# mini64se-v1_0_9-103-2s.net
KiCad netlist of a schematic drawn in EAGLE
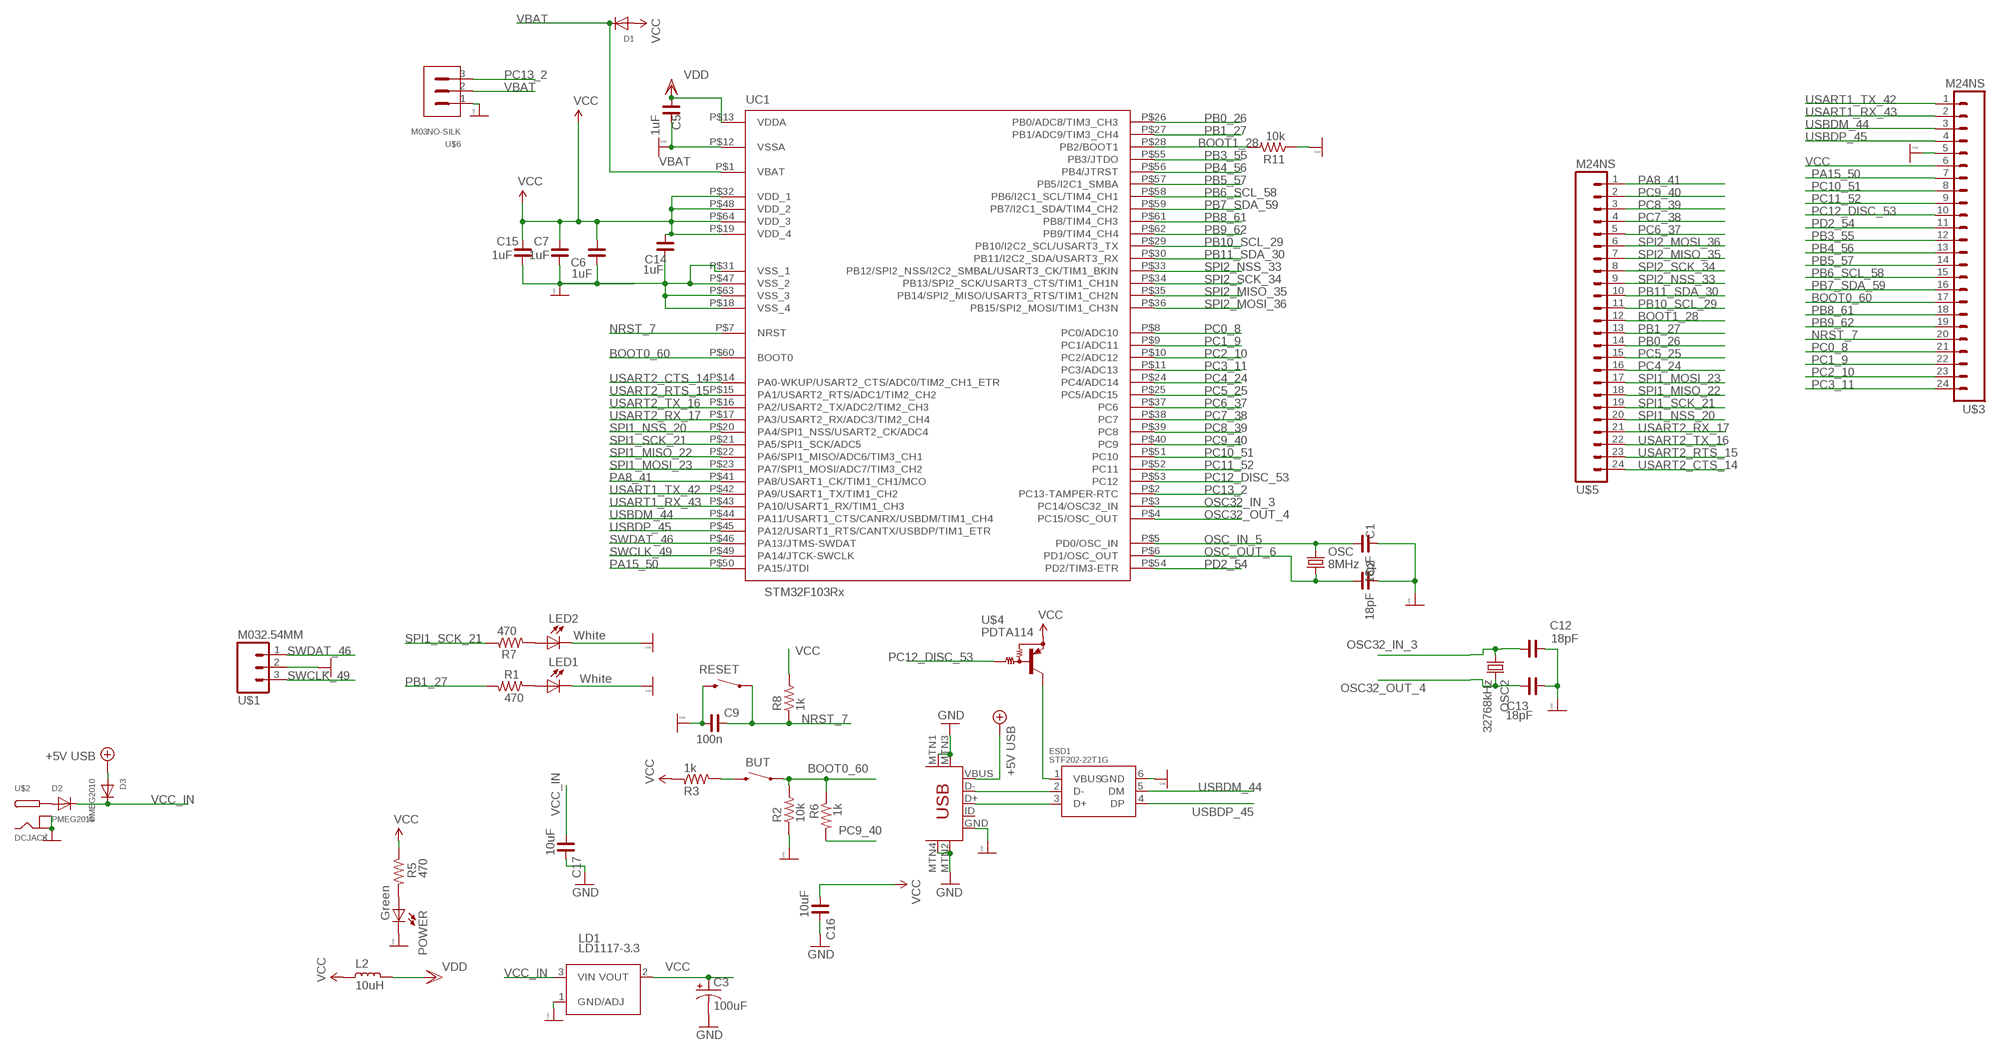
[diagram p0: schematic, sheet 1]

(export (version "E")
  (design (tool "Eeschema 10.0.6"))
  (components
    (comp (ref "BUT")
      (value "SWITCH-MOMENTARY-2SMD")
      (footprint "eagle-import:TACTILE_SWITCH_SMD")
      (libsource (lib "eagle-import") (part "SWITCH-MOMENTARY-2SMD"))
    )
    (comp (ref "C1")
      (value "18pF")
      (footprint "eagle-import:C0603")
      (libsource (lib "eagle-import") (part "C_0603"))
    )
    (comp (ref "C2")
      (value "18pF")
      (footprint "eagle-import:C0603")
      (libsource (lib "eagle-import") (part "C_0603"))
    )
    (comp (ref "C3")
      (value "100uF")
      (footprint "eagle-import:PANASONIC_C")
      (libsource (lib "eagle-import") (part "CAP_POLC"))
    )
    (comp (ref "C5")
      (value "1uF")
      (footprint "eagle-import:C0603")
      (libsource (lib "eagle-import") (part "C_0603"))
    )
    (comp (ref "C6")
      (value "1uF")
      (footprint "eagle-import:C0603")
      (libsource (lib "eagle-import") (part "C_0603"))
    )
    (comp (ref "C7")
      (value "1uF")
      (footprint "eagle-import:C0603")
      (libsource (lib "eagle-import") (part "C_0603"))
    )
    (comp (ref "C9")
      (value "100n")
      (footprint "eagle-import:C0603")
      (libsource (lib "eagle-import") (part "C_0603"))
    )
    (comp (ref "C12")
      (value "18pF")
      (footprint "eagle-import:C0603")
      (libsource (lib "eagle-import") (part "C_0603"))
    )
    (comp (ref "C13")
      (value "18pF")
      (footprint "eagle-import:C0603")
      (libsource (lib "eagle-import") (part "C_0603"))
    )
    (comp (ref "C14")
      (value "1uF")
      (footprint "eagle-import:C0603")
      (libsource (lib "eagle-import") (part "C_0603"))
    )
    (comp (ref "C15")
      (value "1uF")
      (footprint "eagle-import:C0603")
      (libsource (lib "eagle-import") (part "C_0603"))
    )
    (comp (ref "C16")
      (value "10uF")
      (footprint "eagle-import:C0805")
      (libsource (lib "eagle-import") (part "C_0805"))
    )
    (comp (ref "C17")
      (value "10uF")
      (footprint "eagle-import:C0805")
      (libsource (lib "eagle-import") (part "C_0805"))
    )
    (comp (ref "D1")
      (value "DIODESOD-323")
      (footprint "eagle-import:SOD-323")
      (libsource (lib "eagle-import") (part "DIODESOD-323"))
    )
    (comp (ref "D2")
      (value "PMEG2010")
      (footprint "eagle-import:SOD-323")
      (libsource (lib "eagle-import") (part "DIODESOD-323"))
    )
    (comp (ref "D3")
      (value "PMEG2010")
      (footprint "eagle-import:SOD-323")
      (libsource (lib "eagle-import") (part "DIODESOD-323"))
    )
    (comp (ref "ESD1")
      (value "STF202-22T1G")
      (footprint "eagle-import:TSOP-6")
      (libsource (lib "eagle-import") (part "STF202TSOP-6"))
    )
    (comp (ref "L2")
      (value "10uH")
      (footprint "eagle-import:PM0603")
      (libsource (lib "eagle-import") (part "L_PM0603"))
    )
    (comp (ref "LD1")
      (value "LD1117-3.3")
      (footprint "eagle-import:SOT223")
      (libsource (lib "eagle-import") (part "LD1117SOT223"))
    )
    (comp (ref "LED1")
      (value "White")
      (footprint "eagle-import:KA-3528ASYC")
      (libsource (lib "eagle-import") (part "LEDKA-3528ASYC"))
    )
    (comp (ref "LED2")
      (value "White")
      (footprint "eagle-import:KA-3528ASYC")
      (libsource (lib "eagle-import") (part "LEDKA-3528ASYC"))
    )
    (comp (ref "OSC")
      (value "8MHz")
      (footprint "eagle-import:HC49U-V")
      (libsource (lib "eagle-import") (part "CRYSTALHC49UV"))
    )
    (comp (ref "OSC2")
      (value "32768kHz")
      (footprint "eagle-import:TC26H-M")
      (libsource (lib "eagle-import") (part "CRYSTALTC26HM"))
    )
    (comp (ref "POWER")
      (value "Green")
      (footprint "eagle-import:CHIPLED_0603")
      (libsource (lib "eagle-import") (part "LEDCHIPLED_0603"))
    )
    (comp (ref "R1")
      (value "470")
      (footprint "eagle-import:R0603")
      (libsource (lib "eagle-import") (part "R_0603"))
    )
    (comp (ref "R2")
      (value "10k")
      (footprint "eagle-import:R0603")
      (libsource (lib "eagle-import") (part "R_0603"))
    )
    (comp (ref "R3")
      (value "1k")
      (footprint "eagle-import:R0603")
      (libsource (lib "eagle-import") (part "R_0603"))
    )
    (comp (ref "R5")
      (value "470")
      (footprint "eagle-import:R0603")
      (libsource (lib "eagle-import") (part "R_0603"))
    )
    (comp (ref "R6")
      (value "1k")
      (footprint "eagle-import:R0603")
      (libsource (lib "eagle-import") (part "R_0603"))
    )
    (comp (ref "R7")
      (value "470")
      (footprint "eagle-import:R0603")
      (libsource (lib "eagle-import") (part "R_0603"))
    )
    (comp (ref "R8")
      (value "1k")
      (footprint "eagle-import:R0603")
      (libsource (lib "eagle-import") (part "R_0603"))
    )
    (comp (ref "R11")
      (value "10k")
      (footprint "eagle-import:R0603")
      (libsource (lib "eagle-import") (part "R_0603"))
    )
    (comp (ref "RESET")
      (value "SWITCH-MOMENTARY-2SMD")
      (footprint "eagle-import:TACTILE_SWITCH_SMD")
      (libsource (lib "eagle-import") (part "SWITCH-MOMENTARY-2SMD"))
    )
    (comp (ref "U$1")
      (value "M032.54MM")
      (footprint "eagle-import:1X03_NO_SILK")
      (libsource (lib "eagle-import") (part "M031X03_NO_SILK"))
    )
    (comp (ref "U$2")
      (value "DCJACK")
      (footprint "eagle-import:DC-020-001")
      (libsource (lib "eagle-import") (part "DCJACK"))
    )
    (comp (ref "U$3")
      (value "M24NS")
      (footprint "eagle-import:1X24_NO_SILK")
      (libsource (lib "eagle-import") (part "M24NS"))
    )
    (comp (ref "U$4")
      (value "PDTA114")
      (footprint "eagle-import:SOT23-3")
      (libsource (lib "eagle-import") (part "PNP-DRIVERSOT23-3"))
    )
    (comp (ref "U$5")
      (value "M24NS")
      (footprint "eagle-import:1X24_NO_SILK")
      (libsource (lib "eagle-import") (part "M24NS"))
    )
    (comp (ref "U$6")
      (value "M03NO-SILK")
      (footprint "eagle-import:1X03_NO_SILK")
      (libsource (lib "eagle-import") (part "M03NO-SILK"))
    )
    (comp (ref "UC1")
      (value "STM32F103Rx")
      (footprint "eagle-import:TQFP-10X10-64")
      (libsource (lib "eagle-import") (part "STM32F103"))
    )
    (comp (ref "USB")
      (value "USB-MINIB-5PIN")
      (footprint "eagle-import:USB-MINIB")
      (libsource (lib "eagle-import") (part "USB-MINIB-5PIN"))
    )
  )
  (nets
    (net (code "1") (name "+5V USB") (class "Default")
      (node (ref "D3") (pin "A") (pinfunction "A_A") (pintype "passive"))
      (node (ref "USB") (pin "VBUS") (pinfunction "VBUS_VBUS") (pintype "bidirectional"))
    )
    (net (code "2") (name "/BOOT0_60") (class "Default")
      (node (ref "BUT") (pin "1") (pinfunction "1_1") (pintype "passive"))
      (node (ref "R2") (pin "2") (pinfunction "2_2") (pintype "passive"))
      (node (ref "R6") (pin "1") (pinfunction "1_1") (pintype "passive"))
      (node (ref "U$3") (pin "17") (pinfunction "18_17") (pintype "passive"))
      (node (ref "UC1") (pin "P$60") (pinfunction "BOOT0_P$60") (pintype "bidirectional"))
    )
    (net (code "3") (name "/BOOT1_28") (class "Default")
      (node (ref "R11") (pin "2") (pinfunction "2_2") (pintype "passive"))
      (node (ref "U$5") (pin "12") (pinfunction "13_12") (pintype "passive"))
      (node (ref "UC1") (pin "P$28") (pinfunction "PB2/BOOT1_P$28") (pintype "bidirectional"))
    )
    (net (code "4") (name "/NRST_7") (class "Default")
      (node (ref "C9") (pin "2") (pinfunction "2_2") (pintype "passive"))
      (node (ref "R8") (pin "1") (pinfunction "1_1") (pintype "passive"))
      (node (ref "RESET") (pin "1") (pinfunction "1_1") (pintype "passive"))
      (node (ref "U$3") (pin "20") (pinfunction "21_20") (pintype "passive"))
      (node (ref "UC1") (pin "P$7") (pinfunction "NRST_P$7") (pintype "bidirectional"))
    )
    (net (code "5") (name "/OSC32_IN_3") (class "Default")
      (node (ref "C12") (pin "2") (pinfunction "2_2") (pintype "passive"))
      (node (ref "OSC2") (pin "1") (pinfunction "1_1") (pintype "passive"))
      (node (ref "UC1") (pin "P$3") (pinfunction "PC14/OSC32_IN_P$3") (pintype "bidirectional"))
    )
    (net (code "6") (name "/OSC32_OUT_4") (class "Default")
      (node (ref "C13") (pin "2") (pinfunction "2_2") (pintype "passive"))
      (node (ref "OSC2") (pin "2") (pinfunction "2_2") (pintype "passive"))
      (node (ref "UC1") (pin "P$4") (pinfunction "PC15/OSC_OUT_P$4") (pintype "bidirectional"))
    )
    (net (code "7") (name "/OSC_IN_5") (class "Default")
      (node (ref "C1") (pin "2") (pinfunction "2_2") (pintype "passive"))
      (node (ref "OSC") (pin "2") (pinfunction "2_2") (pintype "passive"))
      (node (ref "UC1") (pin "P$5") (pinfunction "PD0/OSC_IN_P$5") (pintype "bidirectional"))
    )
    (net (code "8") (name "/OSC_OUT_6") (class "Default")
      (node (ref "C2") (pin "2") (pinfunction "2_2") (pintype "passive"))
      (node (ref "OSC") (pin "1") (pinfunction "1_1") (pintype "passive"))
      (node (ref "UC1") (pin "P$6") (pinfunction "PD1/OSC_OUT_P$6") (pintype "bidirectional"))
    )
    (net (code "9") (name "/PA8_41") (class "Default")
      (node (ref "U$5") (pin "1") (pinfunction "2_1") (pintype "passive"))
      (node (ref "UC1") (pin "P$41") (pinfunction "PA8/USART1_CK/TIM1_CH1/MCO_P$41") (pintype "bidirectional"))
    )
    (net (code "10") (name "/PA15_50") (class "Default")
      (node (ref "U$3") (pin "7") (pinfunction "8_7") (pintype "passive"))
      (node (ref "UC1") (pin "P$50") (pinfunction "PA15/JTDI_P$50") (pintype "bidirectional"))
    )
    (net (code "11") (name "/PB0_26") (class "Default")
      (node (ref "U$5") (pin "14") (pinfunction "15_14") (pintype "passive"))
      (node (ref "UC1") (pin "P$26") (pinfunction "PB0/ADC8/TIM3_CH3_P$26") (pintype "bidirectional"))
    )
    (net (code "12") (name "/PB1_27") (class "Default")
      (node (ref "R1") (pin "2") (pinfunction "2_2") (pintype "passive"))
      (node (ref "U$5") (pin "13") (pinfunction "14_13") (pintype "passive"))
      (node (ref "UC1") (pin "P$27") (pinfunction "PB1/ADC9/TIM3_CH4_P$27") (pintype "bidirectional"))
    )
    (net (code "13") (name "/PB3_55") (class "Default")
      (node (ref "U$3") (pin "12") (pinfunction "13_12") (pintype "passive"))
      (node (ref "UC1") (pin "P$55") (pinfunction "PB3/JTDO_P$55") (pintype "bidirectional"))
    )
    (net (code "14") (name "/PB4_56") (class "Default")
      (node (ref "U$3") (pin "13") (pinfunction "14_13") (pintype "passive"))
      (node (ref "UC1") (pin "P$56") (pinfunction "PB4/JTRST_P$56") (pintype "bidirectional"))
    )
    (net (code "15") (name "/PB5_57") (class "Default")
      (node (ref "U$3") (pin "14") (pinfunction "15_14") (pintype "passive"))
      (node (ref "UC1") (pin "P$57") (pinfunction "PB5/I2C1_SMBA_P$57") (pintype "bidirectional"))
    )
    (net (code "16") (name "/PB6_SCL_58") (class "Default")
      (node (ref "U$3") (pin "15") (pinfunction "16_15") (pintype "passive"))
      (node (ref "UC1") (pin "P$58") (pinfunction "PB6/I2C1_SCL/TIM4_CH1_P$58") (pintype "bidirectional"))
    )
    (net (code "17") (name "/PB7_SDA_59") (class "Default")
      (node (ref "U$3") (pin "16") (pinfunction "17_16") (pintype "passive"))
      (node (ref "UC1") (pin "P$59") (pinfunction "PB7/I2C1_SDA/TIM4_CH2_P$59") (pintype "bidirectional"))
    )
    (net (code "18") (name "/PB8_61") (class "Default")
      (node (ref "U$3") (pin "18") (pinfunction "19_18") (pintype "passive"))
      (node (ref "UC1") (pin "P$61") (pinfunction "PB8/TIM4_CH3_P$61") (pintype "bidirectional"))
    )
    (net (code "19") (name "/PB9_62") (class "Default")
      (node (ref "U$3") (pin "19") (pinfunction "20_19") (pintype "passive"))
      (node (ref "UC1") (pin "P$62") (pinfunction "PB9/TIM4_CH4_P$62") (pintype "bidirectional"))
    )
    (net (code "20") (name "/PB10_SCL_29") (class "Default")
      (node (ref "U$5") (pin "11") (pinfunction "12_11") (pintype "passive"))
      (node (ref "UC1") (pin "P$29") (pinfunction "PB10/I2C2_SCL/USART3_TX_P$29") (pintype "bidirectional"))
    )
    (net (code "21") (name "/PB11_SDA_30") (class "Default")
      (node (ref "U$5") (pin "10") (pinfunction "11_10") (pintype "passive"))
      (node (ref "UC1") (pin "P$30") (pinfunction "PB11/I2C2_SDA/USART3_RX_P$30") (pintype "bidirectional"))
    )
    (net (code "22") (name "/PC0_8") (class "Default")
      (node (ref "U$3") (pin "21") (pinfunction "22_21") (pintype "passive"))
      (node (ref "UC1") (pin "P$8") (pinfunction "PC0/ADC10_P$8") (pintype "bidirectional"))
    )
    (net (code "23") (name "/PC1_9") (class "Default")
      (node (ref "U$3") (pin "22") (pinfunction "23_22") (pintype "passive"))
      (node (ref "UC1") (pin "P$9") (pinfunction "PC1/ADC11_P$9") (pintype "bidirectional"))
    )
    (net (code "24") (name "/PC2_10") (class "Default")
      (node (ref "U$3") (pin "23") (pinfunction "24_23") (pintype "passive"))
      (node (ref "UC1") (pin "P$10") (pinfunction "PC2/ADC12_P$10") (pintype "bidirectional"))
    )
    (net (code "25") (name "/PC3_11") (class "Default")
      (node (ref "U$3") (pin "24") (pinfunction "25_24") (pintype "passive"))
      (node (ref "UC1") (pin "P$11") (pinfunction "PC3/ADC13_P$11") (pintype "bidirectional"))
    )
    (net (code "26") (name "/PC4_24") (class "Default")
      (node (ref "U$5") (pin "16") (pinfunction "17_16") (pintype "passive"))
      (node (ref "UC1") (pin "P$24") (pinfunction "PC4/ADC14_P$24") (pintype "bidirectional"))
    )
    (net (code "27") (name "/PC5_25") (class "Default")
      (node (ref "U$5") (pin "15") (pinfunction "16_15") (pintype "passive"))
      (node (ref "UC1") (pin "P$25") (pinfunction "PC5/ADC15_P$25") (pintype "bidirectional"))
    )
    (net (code "28") (name "/PC6_37") (class "Default")
      (node (ref "U$5") (pin "5") (pinfunction "6_5") (pintype "passive"))
      (node (ref "UC1") (pin "P$37") (pinfunction "PC6_P$37") (pintype "bidirectional"))
    )
    (net (code "29") (name "/PC7_38") (class "Default")
      (node (ref "U$5") (pin "4") (pinfunction "5_4") (pintype "passive"))
      (node (ref "UC1") (pin "P$38") (pinfunction "PC7_P$38") (pintype "bidirectional"))
    )
    (net (code "30") (name "/PC8_39") (class "Default")
      (node (ref "U$5") (pin "3") (pinfunction "4_3") (pintype "passive"))
      (node (ref "UC1") (pin "P$39") (pinfunction "PC8_P$39") (pintype "bidirectional"))
    )
    (net (code "31") (name "/PC9_40") (class "Default")
      (node (ref "R6") (pin "2") (pinfunction "2_2") (pintype "passive"))
      (node (ref "U$5") (pin "2") (pinfunction "3_2") (pintype "passive"))
      (node (ref "UC1") (pin "P$40") (pinfunction "PC9_P$40") (pintype "bidirectional"))
    )
    (net (code "32") (name "/PC10_51") (class "Default")
      (node (ref "U$3") (pin "8") (pinfunction "9_8") (pintype "passive"))
      (node (ref "UC1") (pin "P$51") (pinfunction "PC10_P$51") (pintype "bidirectional"))
    )
    (net (code "33") (name "/PC11_52") (class "Default")
      (node (ref "U$3") (pin "9") (pinfunction "10_9") (pintype "passive"))
      (node (ref "UC1") (pin "P$52") (pinfunction "PC11_P$52") (pintype "bidirectional"))
    )
    (net (code "34") (name "/PC12_DISC_53") (class "Default")
      (node (ref "U$3") (pin "10") (pinfunction "11_10") (pintype "passive"))
      (node (ref "U$4") (pin "1") (pinfunction "B_1") (pintype "passive"))
      (node (ref "UC1") (pin "P$53") (pinfunction "PC12_P$53") (pintype "bidirectional"))
    )
    (net (code "35") (name "/PC13_2") (class "Default")
      (node (ref "U$6") (pin "3") (pinfunction "3_3") (pintype "bidirectional"))
      (node (ref "UC1") (pin "P$2") (pinfunction "PC13-TAMPER-RTC_P$2") (pintype "bidirectional"))
    )
    (net (code "36") (name "/PD2_54") (class "Default")
      (node (ref "U$3") (pin "11") (pinfunction "12_11") (pintype "passive"))
      (node (ref "UC1") (pin "P$54") (pinfunction "PD2/TIM3-ETR_P$54") (pintype "bidirectional"))
    )
    (net (code "37") (name "/SPI1_MISO_22") (class "Default")
      (node (ref "U$5") (pin "18") (pinfunction "19_18") (pintype "passive"))
      (node (ref "UC1") (pin "P$22") (pinfunction "PA6/SPI1_MISO/ADC6/TIM3_CH1_P$22") (pintype "bidirectional"))
    )
    (net (code "38") (name "/SPI1_MOSI_23") (class "Default")
      (node (ref "U$5") (pin "17") (pinfunction "18_17") (pintype "passive"))
      (node (ref "UC1") (pin "P$23") (pinfunction "PA7/SPI1_MOSI/ADC7/TIM3_CH2_P$23") (pintype "bidirectional"))
    )
    (net (code "39") (name "/SPI1_NSS_20") (class "Default")
      (node (ref "U$5") (pin "20") (pinfunction "21_20") (pintype "passive"))
      (node (ref "UC1") (pin "P$20") (pinfunction "PA4/SPI1_NSS/USART2_CK/ADC4_P$20") (pintype "bidirectional"))
    )
    (net (code "40") (name "/SPI1_SCK_21") (class "Default")
      (node (ref "R7") (pin "1") (pinfunction "1_1") (pintype "passive"))
      (node (ref "U$5") (pin "19") (pinfunction "20_19") (pintype "passive"))
      (node (ref "UC1") (pin "P$21") (pinfunction "PA5/SPI1_SCK/ADC5_P$21") (pintype "bidirectional"))
    )
    (net (code "41") (name "/SPI2_MISO_35") (class "Default")
      (node (ref "U$5") (pin "7") (pinfunction "8_7") (pintype "passive"))
      (node (ref "UC1") (pin "P$35") (pinfunction "PB14/SPI2_MISO/USART3_RTS/TIM1_CH2N_P$35") (pintype "bidirectional"))
    )
    (net (code "42") (name "/SPI2_MOSI_36") (class "Default")
      (node (ref "U$5") (pin "6") (pinfunction "7_6") (pintype "passive"))
      (node (ref "UC1") (pin "P$36") (pinfunction "PB15/SPI2_MOSI/TIM1_CH3N_P$36") (pintype "bidirectional"))
    )
    (net (code "43") (name "/SPI2_NSS_33") (class "Default")
      (node (ref "U$5") (pin "9") (pinfunction "10_9") (pintype "passive"))
      (node (ref "UC1") (pin "P$33") (pinfunction "PB12/SPI2_NSS/I2C2_SMBAL/USART3_CK/TIM1_BKIN_P$33") (pintype "bidirectional"))
    )
    (net (code "44") (name "/SPI2_SCK_34") (class "Default")
      (node (ref "U$5") (pin "8") (pinfunction "9_8") (pintype "passive"))
      (node (ref "UC1") (pin "P$34") (pinfunction "PB13/SPI2_SCK/USART3_CTS/TIM1_CH1N_P$34") (pintype "bidirectional"))
    )
    (net (code "45") (name "/SWCLK_49") (class "Default")
      (node (ref "U$1") (pin "3") (pinfunction "3_3") (pintype "passive"))
      (node (ref "UC1") (pin "P$49") (pinfunction "PA14/JTCK-SWCLK_P$49") (pintype "bidirectional"))
    )
    (net (code "46") (name "/SWDAT_46") (class "Default")
      (node (ref "U$1") (pin "1") (pinfunction "1_1") (pintype "passive"))
      (node (ref "UC1") (pin "P$46") (pinfunction "PA13/JTMS-SWDAT_P$46") (pintype "bidirectional"))
    )
    (net (code "47") (name "/USART1_RX_43") (class "Default")
      (node (ref "U$3") (pin "2") (pinfunction "3_2") (pintype "passive"))
      (node (ref "UC1") (pin "P$43") (pinfunction "PA10/USART1_RX/TIM1_CH3_P$43") (pintype "bidirectional"))
    )
    (net (code "48") (name "/USART1_TX_42") (class "Default")
      (node (ref "U$3") (pin "1") (pinfunction "2_1") (pintype "passive"))
      (node (ref "UC1") (pin "P$42") (pinfunction "PA9/USART1_TX/TIM1_CH2_P$42") (pintype "bidirectional"))
    )
    (net (code "49") (name "/USART2_CTS_14") (class "Default")
      (node (ref "U$5") (pin "24") (pinfunction "25_24") (pintype "passive"))
      (node (ref "UC1") (pin "P$14") (pinfunction "PA0-WKUP/USART2_CTS/ADC0/TIM2_CH1_ETR_P$14") (pintype "bidirectional"))
    )
    (net (code "50") (name "/USART2_RTS_15") (class "Default")
      (node (ref "U$5") (pin "23") (pinfunction "24_23") (pintype "passive"))
      (node (ref "UC1") (pin "P$15") (pinfunction "PA1/USART2_RTS/ADC1/TIM2_CH2_P$15") (pintype "bidirectional"))
    )
    (net (code "51") (name "/USART2_RX_17") (class "Default")
      (node (ref "U$5") (pin "21") (pinfunction "22_21") (pintype "passive"))
      (node (ref "UC1") (pin "P$17") (pinfunction "PA3/USART2_RX/ADC3/TIM2_CH4_P$17") (pintype "bidirectional"))
    )
    (net (code "52") (name "/USART2_TX_16") (class "Default")
      (node (ref "U$5") (pin "22") (pinfunction "23_22") (pintype "passive"))
      (node (ref "UC1") (pin "P$16") (pinfunction "PA2/USART2_TX/ADC2/TIM2_CH3_P$16") (pintype "bidirectional"))
    )
    (net (code "53") (name "/USBDM_44") (class "Default")
      (node (ref "ESD1") (pin "5") (pinfunction "DM_5") (pintype "bidirectional"))
      (node (ref "U$3") (pin "3") (pinfunction "4_3") (pintype "passive"))
      (node (ref "UC1") (pin "P$44") (pinfunction "PA11/USART1_CTS/CANRX/USBDM/TIM1_CH4_P$44") (pintype "bidirectional"))
    )
    (net (code "54") (name "/USBDP_45") (class "Default")
      (node (ref "ESD1") (pin "4") (pinfunction "DP_4") (pintype "bidirectional"))
      (node (ref "U$3") (pin "4") (pinfunction "5_4") (pintype "passive"))
      (node (ref "UC1") (pin "P$45") (pinfunction "PA12/USART1_RTS/CANTX/USBDP/TIM1_ETR_P$45") (pintype "bidirectional"))
    )
    (net (code "55") (name "/VBAT") (class "Default")
      (node (ref "D1") (pin "C") (pinfunction "C_C") (pintype "passive"))
      (node (ref "U$6") (pin "2") (pinfunction "2_2") (pintype "bidirectional"))
      (node (ref "UC1") (pin "P$1") (pinfunction "VBAT_P$1") (pintype "power_in"))
    )
    (net (code "56") (name "/VCC_IN") (class "Default")
      (node (ref "C17") (pin "1") (pinfunction "1_1") (pintype "passive"))
      (node (ref "D2") (pin "C") (pinfunction "C_C") (pintype "passive"))
      (node (ref "D3") (pin "C") (pinfunction "C_C") (pintype "passive"))
      (node (ref "LD1") (pin "3") (pinfunction "VIN_3") (pintype "bidirectional"))
    )
    (net (code "57") (name "GND") (class "Default")
      (node (ref "C1") (pin "1") (pinfunction "1_1") (pintype "passive"))
      (node (ref "C12") (pin "1") (pinfunction "1_1") (pintype "passive"))
      (node (ref "C13") (pin "1") (pinfunction "1_1") (pintype "passive"))
      (node (ref "C14") (pin "1") (pinfunction "1_1") (pintype "passive"))
      (node (ref "C15") (pin "1") (pinfunction "1_1") (pintype "passive"))
      (node (ref "C16") (pin "2") (pinfunction "2_2") (pintype "passive"))
      (node (ref "C17") (pin "2") (pinfunction "2_2") (pintype "passive"))
      (node (ref "C2") (pin "1") (pinfunction "1_1") (pintype "passive"))
      (node (ref "C3") (pin "-") (pinfunction "-_-") (pintype "passive"))
      (node (ref "C5") (pin "1") (pinfunction "1_1") (pintype "passive"))
      (node (ref "C6") (pin "1") (pinfunction "1_1") (pintype "passive"))
      (node (ref "C7") (pin "1") (pinfunction "1_1") (pintype "passive"))
      (node (ref "C9") (pin "1") (pinfunction "1_1") (pintype "passive"))
      (node (ref "ESD1") (pin "6") (pinfunction "GND_6") (pintype "bidirectional"))
      (node (ref "LD1") (pin "1") (pinfunction "GND/ADJ_1") (pintype "bidirectional"))
      (node (ref "LED1") (pin "C") (pinfunction "C_C") (pintype "passive"))
      (node (ref "LED2") (pin "C") (pinfunction "C_C") (pintype "passive"))
      (node (ref "POWER") (pin "C") (pinfunction "C_C") (pintype "passive"))
      (node (ref "R11") (pin "1") (pinfunction "1_1") (pintype "passive"))
      (node (ref "R2") (pin "1") (pinfunction "1_1") (pintype "passive"))
      (node (ref "RESET") (pin "3") (pinfunction "2_3") (pintype "passive"))
      (node (ref "U$1") (pin "2") (pinfunction "2_2") (pintype "passive"))
      (node (ref "U$2") (pin "GND") (pinfunction "GND_GND") (pintype "power_in"))
      (node (ref "U$2") (pin "GNDBREAK") (pinfunction "GNDBREAK_GNDBREAK") (pintype "power_in"))
      (node (ref "U$3") (pin "5") (pinfunction "6_5") (pintype "passive"))
      (node (ref "U$6") (pin "1") (pinfunction "1_1") (pintype "bidirectional"))
      (node (ref "UC1") (pin "P$12") (pinfunction "VSSA_P$12") (pintype "power_in"))
      (node (ref "UC1") (pin "P$18") (pinfunction "VSS_4_P$18") (pintype "power_in"))
      (node (ref "UC1") (pin "P$31") (pinfunction "VSS_1_P$31") (pintype "power_in"))
      (node (ref "UC1") (pin "P$47") (pinfunction "VSS_2_P$47") (pintype "power_in"))
      (node (ref "UC1") (pin "P$63") (pinfunction "VSS_3_P$63") (pintype "power_in"))
      (node (ref "USB") (pin "GND") (pinfunction "GND_GND") (pintype "bidirectional"))
      (node (ref "USB") (pin "MTN1") (pinfunction "MTN2_MTN1") (pintype "bidirectional"))
      (node (ref "USB") (pin "MTN2") (pinfunction "MTN3_MTN2") (pintype "bidirectional"))
      (node (ref "USB") (pin "MTN3") (pinfunction "MTN1_MTN3") (pintype "bidirectional"))
      (node (ref "USB") (pin "MTN4") (pinfunction "MTN4_MTN4") (pintype "bidirectional"))
    )
    (net (code "58") (name "Net-(BUT-2)") (class "Default")
      (node (ref "BUT") (pin "3") (pinfunction "2_3") (pintype "passive"))
      (node (ref "R3") (pin "2") (pinfunction "2_2") (pintype "passive"))
    )
    (net (code "59") (name "Net-(D2-PadA)") (class "Default")
      (node (ref "D2") (pin "A") (pinfunction "A_A") (pintype "passive"))
      (node (ref "U$2") (pin "PWR") (pinfunction "PWR_PWR") (pintype "power_in"))
    )
    (net (code "60") (name "Net-(ESD1-D+)") (class "Default")
      (node (ref "ESD1") (pin "3") (pinfunction "D+_3") (pintype "bidirectional"))
      (node (ref "USB") (pin "D+") (pinfunction "D+_D+") (pintype "bidirectional"))
    )
    (net (code "61") (name "Net-(ESD1-D-)") (class "Default")
      (node (ref "ESD1") (pin "2") (pinfunction "D-_2") (pintype "bidirectional"))
      (node (ref "USB") (pin "D-") (pinfunction "D-_D-") (pintype "bidirectional"))
    )
    (net (code "62") (name "Net-(ESD1-VBUS)") (class "Default")
      (node (ref "ESD1") (pin "1") (pinfunction "VBUS_1") (pintype "bidirectional"))
      (node (ref "U$4") (pin "3") (pinfunction "C_3") (pintype "passive"))
    )
    (net (code "63") (name "Net-(LED1-PadA)") (class "Default")
      (node (ref "LED1") (pin "A") (pinfunction "A_A") (pintype "passive"))
      (node (ref "R1") (pin "1") (pinfunction "1_1") (pintype "passive"))
    )
    (net (code "64") (name "Net-(LED2-PadA)") (class "Default")
      (node (ref "LED2") (pin "A") (pinfunction "A_A") (pintype "passive"))
      (node (ref "R7") (pin "2") (pinfunction "2_2") (pintype "passive"))
    )
    (net (code "65") (name "Net-(POWER-PadA)") (class "Default")
      (node (ref "POWER") (pin "A") (pinfunction "A_A") (pintype "passive"))
      (node (ref "R5") (pin "2") (pinfunction "2_2") (pintype "passive"))
    )
    (net (code "66") (name "VCC") (class "Default")
      (node (ref "C14") (pin "2") (pinfunction "2_2") (pintype "passive"))
      (node (ref "C15") (pin "2") (pinfunction "2_2") (pintype "passive"))
      (node (ref "C16") (pin "1") (pinfunction "1_1") (pintype "passive"))
      (node (ref "C3") (pin "+") (pinfunction "+_+") (pintype "passive"))
      (node (ref "C6") (pin "2") (pinfunction "2_2") (pintype "passive"))
      (node (ref "C7") (pin "2") (pinfunction "2_2") (pintype "passive"))
      (node (ref "D1") (pin "A") (pinfunction "A_A") (pintype "passive"))
      (node (ref "L2") (pin "2") (pinfunction "2_2") (pintype "passive"))
      (node (ref "LD1") (pin "2") (pinfunction "VOUT_2") (pintype "bidirectional"))
      (node (ref "R3") (pin "1") (pinfunction "1_1") (pintype "passive"))
      (node (ref "R5") (pin "1") (pinfunction "1_1") (pintype "passive"))
      (node (ref "R8") (pin "2") (pinfunction "2_2") (pintype "passive"))
      (node (ref "U$3") (pin "6") (pinfunction "7_6") (pintype "passive"))
      (node (ref "U$4") (pin "2") (pinfunction "E_2") (pintype "passive"))
      (node (ref "UC1") (pin "P$19") (pinfunction "VDD_4_P$19") (pintype "power_in"))
      (node (ref "UC1") (pin "P$32") (pinfunction "VDD_1_P$32") (pintype "power_in"))
      (node (ref "UC1") (pin "P$48") (pinfunction "VDD_2_P$48") (pintype "power_in"))
      (node (ref "UC1") (pin "P$64") (pinfunction "VDD_3_P$64") (pintype "power_in"))
    )
    (net (code "67") (name "VDD") (class "Default")
      (node (ref "C5") (pin "2") (pinfunction "2_2") (pintype "passive"))
      (node (ref "L2") (pin "1") (pinfunction "1_1") (pintype "passive"))
      (node (ref "UC1") (pin "P$13") (pinfunction "VDDA_P$13") (pintype "power_in"))
    )
    (net (code "68") (name "unconnected-(USB-PadID)") (class "Default")
      (node (ref "USB") (pin "ID") (pinfunction "ID_ID") (pintype "bidirectional"))
    )
  )
)
